# TSAL.net
KiCad netlist of a schematic drawn in Altium Designer
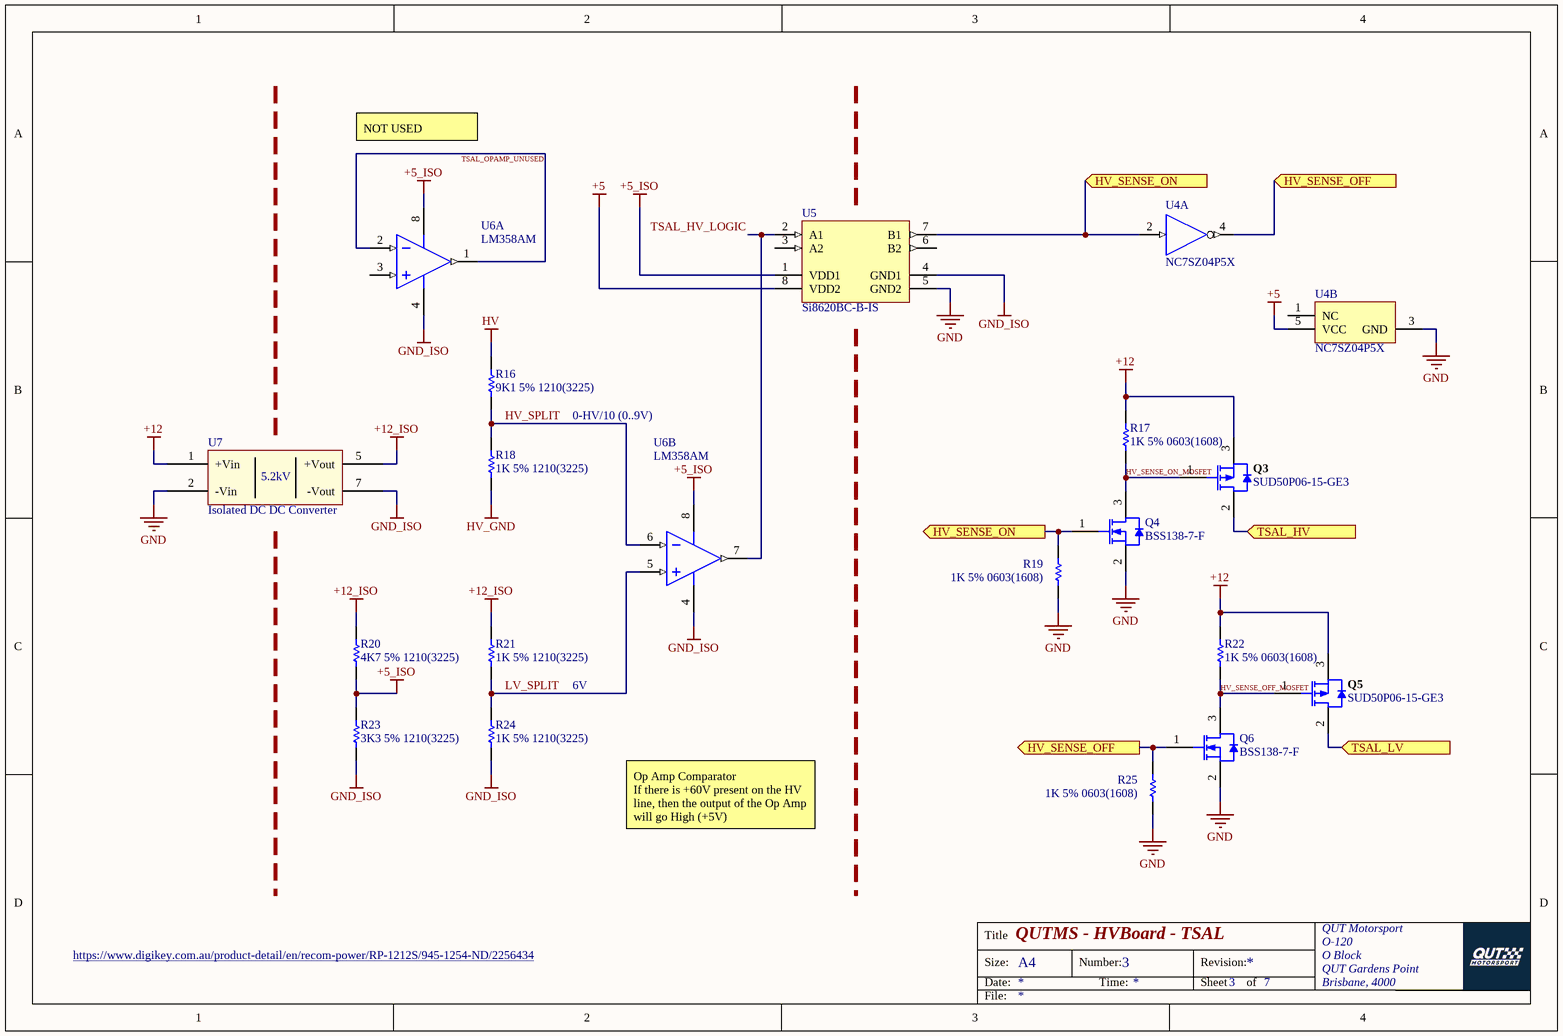
[diagram p0: TSAL.SchDoc]

(export (version "E")
  (design (tool "Eeschema 10.0.6"))
  (components
    (comp (ref "Q3")
      (value "SUD50P06-15-GE3")
      (footprint "VSIL-TO-252AA-3_V")
      (description "P-Channel (D-S) MOSFET, 30 V, -55 to 150 degC, 3-Pin TO-252, RoHS, Tape and Reel")
      (fields (field (name "MANUFACTURER") "Vishay"))
      (libsource (lib "Altium Content Vault") (part "PEMOS-GDS-3"))
    )
    (comp (ref "Q4")
      (value "BSS138-7-F")
      (footprint "DIOD-SOT23-3_V")
      (description "N-Channel Enhancement Mode Mosfet, 50 V, 0.2 A, -55 to 150 degC, 3-Pin SOT23, RoHS, Tape and Reel")
      (fields (field (name "MANUFACTURER") "Diodes Inc"))
      (libsource (lib "Altium Content Vault") (part "NEMOS-GSD-3"))
    )
    (comp (ref "Q5")
      (value "SUD50P06-15-GE3")
      (footprint "VSIL-TO-252AA-3_V")
      (description "P-Channel (D-S) MOSFET, 30 V, -55 to 150 degC, 3-Pin TO-252, RoHS, Tape and Reel")
      (fields (field (name "MANUFACTURER") "Vishay"))
      (libsource (lib "Altium Content Vault") (part "PEMOS-GDS-3"))
    )
    (comp (ref "Q6")
      (value "BSS138-7-F")
      (footprint "DIOD-SOT23-3_V")
      (description "N-Channel Enhancement Mode Mosfet, 50 V, 0.2 A, -55 to 150 degC, 3-Pin SOT23, RoHS, Tape and Reel")
      (fields (field (name "MANUFACTURER") "Diodes Inc"))
      (libsource (lib "Altium Content Vault") (part "NEMOS-GSD-3"))
    )
    (comp (ref "R16")
      (value "9K1 5% 1210(3225)")
      (footprint "RESC1210(3225)_N")
      (description "9K1 0.5W 5% 1210 (3225 Metric)  SMD")
      (fields (field (name "POWER") "0.5 W") (field (name "TOLERANCE") "5 %"))
      (libsource (lib "Altium Content Vault") (part "RES"))
    )
    (comp (ref "R17")
      (value "1K 5% 0603(1608)")
      (footprint "RESC0603(1608)_L")
      (description "1K 0.1W 5% 0603 (1608 Metric)  SMD")
      (fields (field (name "TOLERANCE") "5 %") (field (name "POWER") "0.1 W"))
      (libsource (lib "Altium Content Vault") (part "RES"))
    )
    (comp (ref "R18")
      (value "1K 5% 1210(3225)")
      (footprint "RESC1210(3225)_N")
      (description "1K 0.5W 5% 1210 (3225 Metric)  SMD")
      (fields (field (name "POWER") "0.5 W") (field (name "TOLERANCE") "5 %"))
      (libsource (lib "Altium Content Vault") (part "RES"))
    )
    (comp (ref "R19")
      (value "1K 5% 0603(1608)")
      (footprint "RESC0603(1608)_L")
      (description "1K 0.1W 5% 0603 (1608 Metric)  SMD")
      (fields (field (name "TOLERANCE") "5 %") (field (name "POWER") "0.1 W"))
      (libsource (lib "Altium Content Vault") (part "RES"))
    )
    (comp (ref "R20")
      (value "4K7 5% 1210(3225)")
      (footprint "RESC1210(3225)_N")
      (description "4K7 0.5W 5% 1210 (3225 Metric)  SMD")
      (fields (field (name "TOLERANCE") "5 %") (field (name "POWER") "0.5 W"))
      (libsource (lib "Altium Content Vault") (part "RES"))
    )
    (comp (ref "R21")
      (value "1K 5% 1210(3225)")
      (footprint "RESC1210(3225)_N")
      (description "1K 0.5W 5% 1210 (3225 Metric)  SMD")
      (fields (field (name "POWER") "0.5 W") (field (name "TOLERANCE") "5 %"))
      (libsource (lib "Altium Content Vault") (part "RES"))
    )
    (comp (ref "R22")
      (value "1K 5% 0603(1608)")
      (footprint "RESC0603(1608)_L")
      (description "1K 0.1W 5% 0603 (1608 Metric)  SMD")
      (fields (field (name "TOLERANCE") "5 %") (field (name "POWER") "0.1 W"))
      (libsource (lib "Altium Content Vault") (part "RES"))
    )
    (comp (ref "R23")
      (value "3K3 5% 1210(3225)")
      (footprint "RESC1210(3225)_N")
      (description "3K3 0.5W 5% 1210 (3225 Metric)  SMD")
      (fields (field (name "TOLERANCE") "5 %") (field (name "POWER") "0.5 W"))
      (libsource (lib "Altium Content Vault") (part "RES"))
    )
    (comp (ref "R24")
      (value "1K 5% 1210(3225)")
      (footprint "RESC1210(3225)_N")
      (description "1K 0.5W 5% 1210 (3225 Metric)  SMD")
      (fields (field (name "POWER") "0.5 W") (field (name "TOLERANCE") "5 %"))
      (libsource (lib "Altium Content Vault") (part "RES"))
    )
    (comp (ref "R25")
      (value "1K 5% 0603(1608)")
      (footprint "RESC0603(1608)_L")
      (description "1K 0.1W 5% 0603 (1608 Metric)  SMD")
      (fields (field (name "TOLERANCE") "5 %") (field (name "POWER") "0.1 W"))
      (libsource (lib "Altium Content Vault") (part "RES"))
    )
    (comp (ref "U4")
      (value "NC7SZ04P5X")
      (footprint "FAIR-SC70-5_V")
      (fields (field (name "MANUFACTURER") "FairchildSemiconductor"))
      (libsource (lib "Altium Content Vault") (part "FAIR-NC7SX04-5"))
    )
    (comp (ref "U5")
      (value "Si8620BC-B-IS")
      (footprint "SLAB-SOIC-8-NB_M")
      (fields (field (name "MANUFACTURER") "Silicon Labs"))
      (libsource (lib "Altium Content Vault") (part "SLAB-Si8X20XX-SOIC-8-8"))
    )
    (comp (ref "U6")
      (value "LM358AM")
      (footprint "D0008A_N")
      (description "Low Power Dual Operational Amplifier, 8-pin Narrow SOIC")
      (fields (field (name "MANUFACTURER") "Texas Instruments"))
      (libsource (lib "Altium Content Vault") (part "AMP-OPA-LM158-8"))
    )
    (comp (ref "U7")
      (value "Isolated DC DC Converter")
      (footprint "RP1212S")
      (libsource (lib "QUTMS_IsolatedPowerSupply") (part "RP-1212S"))
    )
  )
  (nets
    (net (code "1") (name "+5") (class "Default")
      (node (ref "U4") (pin "5") (pinfunction "VCC_5") (pintype "power_in"))
      (node (ref "U5") (pin "8") (pinfunction "VDD2_8") (pintype "power_in"))
    )
    (net (code "2") (name "+5_ISO") (class "Default")
      (node (ref "R20") (pin "1") (pinfunction "1_1") (pintype "passive"))
      (node (ref "R23") (pin "2") (pinfunction "2_2") (pintype "passive"))
      (node (ref "U5") (pin "1") (pinfunction "VDD1_1") (pintype "power_in"))
      (node (ref "U6") (pin "8") (pinfunction "V+_8") (pintype "power_in"))
    )
    (net (code "3") (name "+12") (class "Default")
      (node (ref "Q3") (pin "3") (pinfunction "S_3") (pintype "passive"))
      (node (ref "Q5") (pin "3") (pinfunction "S_3") (pintype "passive"))
      (node (ref "R17") (pin "2") (pinfunction "2_2") (pintype "passive"))
      (node (ref "R22") (pin "2") (pinfunction "2_2") (pintype "passive"))
      (node (ref "U7") (pin "1") (pinfunction "+Vin_1") (pintype "passive"))
    )
    (net (code "4") (name "+12_ISO") (class "Default")
      (node (ref "R20") (pin "2") (pinfunction "2_2") (pintype "passive"))
      (node (ref "R21") (pin "2") (pinfunction "2_2") (pintype "passive"))
      (node (ref "U7") (pin "5") (pinfunction "+Vout_5") (pintype "passive"))
    )
    (net (code "5") (name "/HV_SENSE_OFF") (class "Default")
      (node (ref "Q6") (pin "1") (pinfunction "G_1") (pintype "passive"))
      (node (ref "R25") (pin "2") (pinfunction "2_2") (pintype "passive"))
      (node (ref "U4") (pin "4") (pinfunction "Y_4") (pintype "output"))
    )
    (net (code "6") (name "/HV_SENSE_OFF_MOSFET") (class "Default")
      (node (ref "Q5") (pin "1") (pinfunction "G_1") (pintype "passive"))
      (node (ref "Q6") (pin "3") (pinfunction "D_3") (pintype "passive"))
      (node (ref "R22") (pin "1") (pinfunction "1_1") (pintype "passive"))
    )
    (net (code "7") (name "/HV_SENSE_ON") (class "Default")
      (node (ref "Q4") (pin "1") (pinfunction "G_1") (pintype "passive"))
      (node (ref "R19") (pin "2") (pinfunction "2_2") (pintype "passive"))
      (node (ref "U4") (pin "2") (pinfunction "A_2") (pintype "input"))
      (node (ref "U5") (pin "7") (pinfunction "B1_7") (pintype "output"))
    )
    (net (code "8") (name "/HV_SENSE_ON_MOSFET") (class "Default")
      (node (ref "Q3") (pin "1") (pinfunction "G_1") (pintype "passive"))
      (node (ref "Q4") (pin "3") (pinfunction "D_3") (pintype "passive"))
      (node (ref "R17") (pin "1") (pinfunction "1_1") (pintype "passive"))
    )
    (net (code "9") (name "/HV_SPLIT") (class "Default")
      (node (ref "R16") (pin "1") (pinfunction "1_1") (pintype "passive"))
      (node (ref "R18") (pin "2") (pinfunction "2_2") (pintype "passive"))
      (node (ref "U6") (pin "6") (pinfunction "INB-_6") (pintype "input"))
    )
    (net (code "10") (name "/LV_SPLIT") (class "Default")
      (node (ref "R21") (pin "1") (pinfunction "1_1") (pintype "passive"))
      (node (ref "R24") (pin "2") (pinfunction "2_2") (pintype "passive"))
      (node (ref "U6") (pin "5") (pinfunction "INB+_5") (pintype "input"))
    )
    (net (code "11") (name "/TSAL_HV") (class "Default")
      (node (ref "Q3") (pin "2") (pinfunction "D_2") (pintype "passive"))
    )
    (net (code "12") (name "/TSAL_HV_LOGIC") (class "Default")
      (node (ref "U5") (pin "2") (pinfunction "A1_2") (pintype "input"))
      (node (ref "U6") (pin "7") (pinfunction "OUTB_7") (pintype "output"))
    )
    (net (code "13") (name "/TSAL_LV") (class "Default")
      (node (ref "Q5") (pin "2") (pinfunction "D_2") (pintype "passive"))
    )
    (net (code "14") (name "/TSAL_OPAMP_UNUSED") (class "Default")
      (node (ref "U6") (pin "1") (pinfunction "OUTA_1") (pintype "output"))
      (node (ref "U6") (pin "2") (pinfunction "INA-_2") (pintype "input"))
    )
    (net (code "15") (name "GND") (class "Default")
      (node (ref "Q4") (pin "2") (pinfunction "S_2") (pintype "passive"))
      (node (ref "Q6") (pin "2") (pinfunction "S_2") (pintype "passive"))
      (node (ref "R19") (pin "1") (pinfunction "1_1") (pintype "passive"))
      (node (ref "R25") (pin "1") (pinfunction "1_1") (pintype "passive"))
      (node (ref "U4") (pin "3") (pinfunction "GND_3") (pintype "power_in"))
      (node (ref "U5") (pin "5") (pinfunction "GND2_5") (pintype "power_in"))
      (node (ref "U7") (pin "2") (pinfunction "-Vin_2") (pintype "passive"))
    )
    (net (code "16") (name "GND_ISO") (class "Default")
      (node (ref "R23") (pin "1") (pinfunction "1_1") (pintype "passive"))
      (node (ref "R24") (pin "1") (pinfunction "1_1") (pintype "passive"))
      (node (ref "U5") (pin "4") (pinfunction "GND1_4") (pintype "power_in"))
      (node (ref "U6") (pin "4") (pinfunction "GND_4") (pintype "power_in"))
      (node (ref "U7") (pin "7") (pinfunction "-Vout_7") (pintype "passive"))
    )
    (net (code "17") (name "HV") (class "Default")
      (node (ref "R16") (pin "2") (pinfunction "2_2") (pintype "passive"))
    )
    (net (code "18") (name "HV_GND") (class "Default")
      (node (ref "R18") (pin "1") (pinfunction "1_1") (pintype "passive"))
    )
    (net (code "19") (name "unconnected-(U4B-NC-Pad1)") (class "Default")
      (node (ref "U4") (pin "1") (pinfunction "NC_1") (pintype "power_in"))
    )
    (net (code "20") (name "unconnected-(U5-A2-Pad3)") (class "Default")
      (node (ref "U5") (pin "3") (pinfunction "A2_3") (pintype "input"))
    )
    (net (code "21") (name "unconnected-(U5-B2-Pad6)") (class "Default")
      (node (ref "U5") (pin "6") (pinfunction "B2_6") (pintype "output"))
    )
    (net (code "22") (name "unconnected-(U6A-INA+-Pad3)") (class "Default")
      (node (ref "U6") (pin "3") (pinfunction "INA+_3") (pintype "input"))
    )
  )
)
